# Energyharvesting.net
KiCad netlist of a schematic drawn in Altium Designer
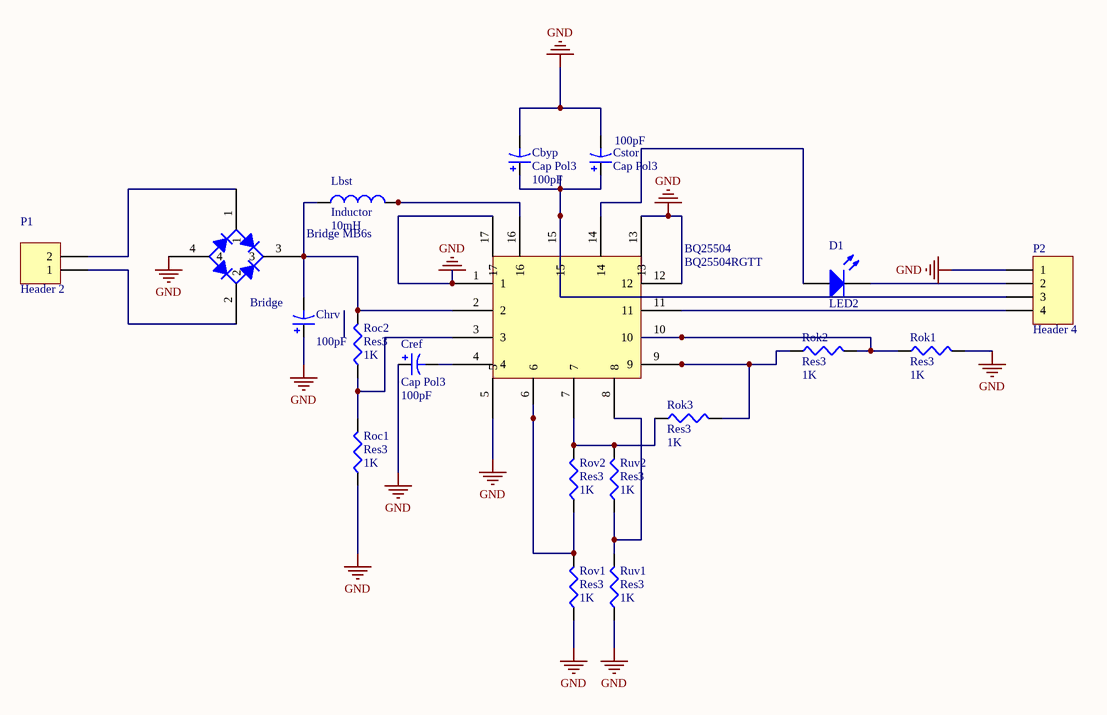
[diagram p0: Energyharvesting.SchDoc]

(export (version "E")
  (design (tool "Eeschema 10.0.6"))
  (components
    (comp (ref "BQ25504")
      (value "BQ25504RGTT")
      (footprint "BQ25504rgtt")
      (libsource (lib "Schlib1") (part "BQ25504RGTT"))
    )
    (comp (ref "Bridge")
      (value "Bridge MB6s")
      (footprint "MB6S")
      (libsource (lib "Schlib1") (part "Bridge MB6s"))
    )
    (comp (ref "Cbyp")
      (value "Cap Pol3")
      (footprint "C0805")
      (description "Polarized Capacitor (Surface Mount)")
      (fields (field (name "ALTIUM_VALUE") "100pF") (field (name "PUBLISHER") "Altium Limited"))
      (libsource (lib "Miscellaneous Devices") (part "Cap Pol3"))
    )
    (comp (ref "Chrv")
      (value "100pF")
      (footprint "C0805")
      (description "Polarized Capacitor (Surface Mount)")
      (fields (field (name "Comment") "Cap Pol3") (field (name "PUBLISHER") "Altium Limited"))
      (libsource (lib "Miscellaneous Devices") (part "Cap Pol3"))
    )
    (comp (ref "Cref")
      (value "Cap Pol3")
      (footprint "C0805")
      (description "Polarized Capacitor (Surface Mount)")
      (fields (field (name "ALTIUM_VALUE") "100pF") (field (name "PUBLISHER") "Altium Limited"))
      (libsource (lib "Miscellaneous Devices") (part "Cap Pol3"))
    )
    (comp (ref "Cstor")
      (value "Cap Pol3")
      (footprint "C0805")
      (description "Polarized Capacitor (Surface Mount)")
      (fields (field (name "ALTIUM_VALUE") "100pF") (field (name "PUBLISHER") "Altium Limited"))
      (libsource (lib "Miscellaneous Devices") (part "Cap Pol3"))
    )
    (comp (ref "D1")
      (value "LED2")
      (footprint "3.2X1.6X1.1")
      (description "Typical RED, GREEN, YELLOW, AMBER GaAs LED")
      (fields (field (name "PUBLISHER") "Altium Limited"))
      (libsource (lib "Miscellaneous Devices") (part "LED2"))
    )
    (comp (ref "Lbst")
      (value "Inductor")
      (footprint "INDC1608L")
      (fields (field (name "ALTIUM_VALUE") "10mH") (field (name "PUBLISHER") "Altium Limited"))
      (libsource (lib "Miscellaneous Devices") (part "Inductor"))
    )
    (comp (ref "P1")
      (value "Header 2")
      (footprint "HDR1X2")
      (description "Header, 2-Pin")
      (fields (field (name "PUBLISHER") "Altium Limited"))
      (libsource (lib "Miscellaneous Connectors") (part "Header 2"))
    )
    (comp (ref "P2")
      (value "Header 4")
      (footprint "HDR1X4")
      (description "Header, 4-Pin")
      (fields (field (name "PUBLISHER") "Altium Limited"))
      (libsource (lib "Miscellaneous Connectors") (part "Header 4"))
    )
    (comp (ref "Roc1")
      (value "Res3")
      (footprint "J1-0603")
      (description "Resistor")
      (fields (field (name "ALTIUM_VALUE") "1K") (field (name "PUBLISHER") "Altium Limited"))
      (libsource (lib "Miscellaneous Devices") (part "Res3"))
    )
    (comp (ref "Roc2")
      (value "Res3")
      (footprint "J1-0603")
      (description "Resistor")
      (fields (field (name "ALTIUM_VALUE") "1K") (field (name "PUBLISHER") "Altium Limited"))
      (libsource (lib "Miscellaneous Devices") (part "Res3"))
    )
    (comp (ref "Rok1")
      (value "Res3")
      (footprint "J1-0603")
      (description "Resistor")
      (fields (field (name "ALTIUM_VALUE") "1K") (field (name "PUBLISHER") "Altium Limited"))
      (libsource (lib "Miscellaneous Devices") (part "Res3"))
    )
    (comp (ref "Rok2")
      (value "Res3")
      (footprint "J1-0603")
      (description "Resistor")
      (fields (field (name "ALTIUM_VALUE") "1K") (field (name "PUBLISHER") "Altium Limited"))
      (libsource (lib "Miscellaneous Devices") (part "Res3"))
    )
    (comp (ref "Rok3")
      (value "Res3")
      (footprint "J1-0603")
      (description "Resistor")
      (fields (field (name "ALTIUM_VALUE") "1K") (field (name "PUBLISHER") "Altium Limited"))
      (libsource (lib "Miscellaneous Devices") (part "Res3"))
    )
    (comp (ref "Rov1")
      (value "Res3")
      (footprint "J1-0603")
      (description "Resistor")
      (fields (field (name "ALTIUM_VALUE") "1K") (field (name "PUBLISHER") "Altium Limited"))
      (libsource (lib "Miscellaneous Devices") (part "Res3"))
    )
    (comp (ref "Rov2")
      (value "Res3")
      (footprint "J1-0603")
      (description "Resistor")
      (fields (field (name "ALTIUM_VALUE") "1K") (field (name "PUBLISHER") "Altium Limited"))
      (libsource (lib "Miscellaneous Devices") (part "Res3"))
    )
    (comp (ref "Ruv1")
      (value "Res3")
      (footprint "J1-0603")
      (description "Resistor")
      (fields (field (name "ALTIUM_VALUE") "1K") (field (name "PUBLISHER") "Altium Limited"))
      (libsource (lib "Miscellaneous Devices") (part "Res3"))
    )
    (comp (ref "Ruv2")
      (value "Res3")
      (footprint "J1-0603")
      (description "Resistor")
      (fields (field (name "ALTIUM_VALUE") "1K") (field (name "PUBLISHER") "Altium Limited"))
      (libsource (lib "Miscellaneous Devices") (part "Res3"))
    )
  )
  (nets
    (net (code "1") (name "GND") (class "Default")
      (node (ref "BQ25504") (pin "1") (pinfunction "1_1") (pintype "passive"))
      (node (ref "BQ25504") (pin "12") (pinfunction "12_12") (pintype "passive"))
      (node (ref "BQ25504") (pin "13") (pinfunction "13_13") (pintype "passive"))
      (node (ref "BQ25504") (pin "17") (pinfunction "17_17") (pintype "passive"))
      (node (ref "BQ25504") (pin "5") (pinfunction "5_5") (pintype "passive"))
      (node (ref "Bridge") (pin "4") (pinfunction "4_4") (pintype "passive"))
      (node (ref "Cbyp") (pin "2") (pinfunction "2_2") (pintype "passive"))
      (node (ref "Chrv") (pin "1") (pinfunction "1_1") (pintype "passive"))
      (node (ref "Cref") (pin "1") (pinfunction "1_1") (pintype "passive"))
      (node (ref "Cstor") (pin "2") (pinfunction "2_2") (pintype "passive"))
      (node (ref "P2") (pin "1") (pinfunction "1_1") (pintype "passive"))
      (node (ref "Roc1") (pin "1") (pinfunction "1_1") (pintype "passive"))
      (node (ref "Rok1") (pin "2") (pinfunction "2_2") (pintype "passive"))
      (node (ref "Rov1") (pin "1") (pinfunction "1_1") (pintype "passive"))
      (node (ref "Ruv1") (pin "1") (pinfunction "1_1") (pintype "passive"))
    )
    (net (code "2") (name "Net-(BQ25504-Pad2)") (class "Default")
      (node (ref "BQ25504") (pin "2") (pinfunction "2_2") (pintype "passive"))
      (node (ref "Bridge") (pin "3") (pinfunction "3_3") (pintype "passive"))
      (node (ref "Chrv") (pin "2") (pinfunction "2_2") (pintype "passive"))
      (node (ref "Lbst") (pin "1") (pinfunction "1_1") (pintype "passive"))
      (node (ref "Roc2") (pin "2") (pinfunction "2_2") (pintype "passive"))
    )
    (net (code "3") (name "Net-(BQ25504-Pad3)") (class "Default")
      (node (ref "BQ25504") (pin "3") (pinfunction "3_3") (pintype "passive"))
      (node (ref "Roc1") (pin "2") (pinfunction "2_2") (pintype "passive"))
      (node (ref "Roc2") (pin "1") (pinfunction "1_1") (pintype "passive"))
    )
    (net (code "4") (name "Net-(BQ25504-Pad4)") (class "Default")
      (node (ref "BQ25504") (pin "4") (pinfunction "4_4") (pintype "passive"))
      (node (ref "Cref") (pin "2") (pinfunction "2_2") (pintype "passive"))
    )
    (net (code "5") (name "Net-(BQ25504-Pad6)") (class "Default")
      (node (ref "BQ25504") (pin "6") (pinfunction "6_6") (pintype "passive"))
      (node (ref "Rov1") (pin "2") (pinfunction "2_2") (pintype "passive"))
      (node (ref "Rov2") (pin "1") (pinfunction "1_1") (pintype "passive"))
    )
    (net (code "6") (name "Net-(BQ25504-Pad7)") (class "Default")
      (node (ref "BQ25504") (pin "7") (pinfunction "7_7") (pintype "passive"))
      (node (ref "Rok3") (pin "1") (pinfunction "1_1") (pintype "passive"))
      (node (ref "Rov2") (pin "2") (pinfunction "2_2") (pintype "passive"))
      (node (ref "Ruv2") (pin "2") (pinfunction "2_2") (pintype "passive"))
    )
    (net (code "7") (name "Net-(BQ25504-Pad8)") (class "Default")
      (node (ref "BQ25504") (pin "8") (pinfunction "8_8") (pintype "passive"))
      (node (ref "Ruv1") (pin "2") (pinfunction "2_2") (pintype "passive"))
      (node (ref "Ruv2") (pin "1") (pinfunction "1_1") (pintype "passive"))
    )
    (net (code "8") (name "Net-(BQ25504-Pad9)") (class "Default")
      (node (ref "BQ25504") (pin "9") (pinfunction "9_9") (pintype "passive"))
      (node (ref "Rok2") (pin "1") (pinfunction "1_1") (pintype "passive"))
      (node (ref "Rok3") (pin "2") (pinfunction "2_2") (pintype "passive"))
    )
    (net (code "9") (name "Net-(BQ25504-Pad10)") (class "Default")
      (node (ref "BQ25504") (pin "10") (pinfunction "10_10") (pintype "passive"))
      (node (ref "Rok1") (pin "1") (pinfunction "1_1") (pintype "passive"))
      (node (ref "Rok2") (pin "2") (pinfunction "2_2") (pintype "passive"))
    )
    (net (code "10") (name "Net-(BQ25504-Pad11)") (class "Default")
      (node (ref "BQ25504") (pin "11") (pinfunction "11_11") (pintype "passive"))
      (node (ref "P2") (pin "4") (pinfunction "4_4") (pintype "passive"))
    )
    (net (code "11") (name "Net-(BQ25504-Pad15)") (class "Default")
      (node (ref "BQ25504") (pin "15") (pinfunction "15_15") (pintype "passive"))
      (node (ref "Cbyp") (pin "1") (pinfunction "1_1") (pintype "passive"))
      (node (ref "Cstor") (pin "1") (pinfunction "1_1") (pintype "passive"))
      (node (ref "P2") (pin "3") (pinfunction "3_3") (pintype "passive"))
    )
    (net (code "12") (name "Net-(BQ25504-Pad16)") (class "Default")
      (node (ref "BQ25504") (pin "16") (pinfunction "16_16") (pintype "passive"))
      (node (ref "Lbst") (pin "2") (pinfunction "2_2") (pintype "passive"))
    )
    (net (code "13") (name "Net-(Bridge-Pad1)") (class "Default")
      (node (ref "Bridge") (pin "1") (pinfunction "1_1") (pintype "passive"))
      (node (ref "P1") (pin "2") (pinfunction "2_2") (pintype "passive"))
    )
    (net (code "14") (name "Net-(Bridge-Pad2)") (class "Default")
      (node (ref "Bridge") (pin "2") (pinfunction "2_2") (pintype "passive"))
      (node (ref "P1") (pin "1") (pinfunction "1_1") (pintype "passive"))
    )
    (net (code "15") (name "Net-(D1-A)") (class "Default")
      (node (ref "BQ25504") (pin "14") (pinfunction "14_14") (pintype "passive"))
      (node (ref "D1") (pin "1") (pinfunction "A_1") (pintype "passive"))
    )
    (net (code "16") (name "Net-(D1-K)") (class "Default")
      (node (ref "D1") (pin "2") (pinfunction "K_2") (pintype "passive"))
      (node (ref "P2") (pin "2") (pinfunction "2_2") (pintype "passive"))
    )
  )
)
